# FPP_Connector.net
KiCad netlist of a schematic drawn in Altium Designer
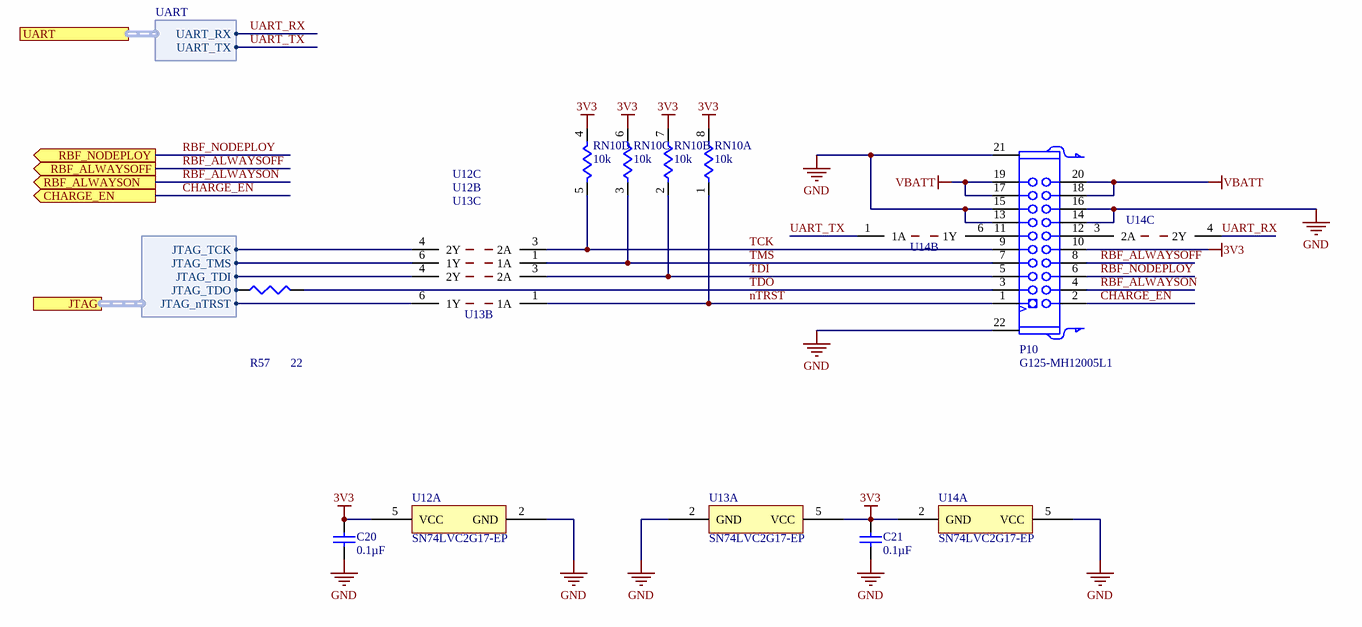
[diagram p0: FPP Connector.SchDoc]

(export (version "E")
  (design (tool "Eeschema 10.0.6"))
  (components
    (comp (ref "C20")
      (value "0.1µF")
      (footprint "TDK-CGA2B")
      (description "CAP CER 0.1UF 50V X7R 0402")
      (fields
        (field (name "PART NUMBER") "PC-TDK-02259")
        (field (name "MANUFACTURER PART NUMBER") "CGA2B3X7R1H104K050BB")
        (field (name "PUBLISHER") "AlbertaSat")
      )
      (libsource (lib "Database") (part "Cap"))
    )
    (comp (ref "C21")
      (value "0.1µF")
      (footprint "TDK-CGA2B")
      (description "CAP CER 0.1UF 50V X7R 0402")
      (fields
        (field (name "PART NUMBER") "PC-TDK-02259")
        (field (name "MANUFACTURER PART NUMBER") "CGA2B3X7R1H104K050BB")
        (field (name "PUBLISHER") "AlbertaSat")
      )
      (libsource (lib "Database") (part "Cap"))
    )
    (comp (ref "P10")
      (value "G125-MH12005L1")
      (footprint "HWN-G125-MH12005L1")
      (description "CONN HEADER R/A 20POS 1.25MM")
      (fields
        (field (name "PART NUMBER") "PP-HWN-00018")
        (field (name "MANUFACTURER PART NUMBER") "G125-MH12005L1P")
        (field (name "PUBLISHER") "AlbertaSat")
      )
      (libsource (lib "Database") (part "G125-MH12005L1P"))
    )
    (comp (ref "R57")
      (value "22")
      (footprint "PANA-ERJ2R")
      (description "RES SMD 22 OHM 1% 1/10W 0402")
      (fields
        (field (name "PART NUMBER") "13460")
        (field (name "MANUFACTURER PART NUMBER") "ERJ-2RKF22R0X")
        (field (name "PUBLISHER") "Altium Limited")
      )
      (libsource (lib "Database") (part "Res3"))
    )
    (comp (ref "RN10")
      (value "10k")
      (footprint "PANA-EXB28V")
      (description "RES ARRAY 4 RES 10K OHM 0804")
      (fields (field (name "PART NUMBER") "19968") (field (name "MANUFACTURER PART NUMBER") "EXB-28V103JX"))
      (libsource (lib "Database") (part "Res4 Pack1"))
    )
    (comp (ref "U12")
      (value "SN74LVC2G17-EP")
      (footprint "TI-R-PDSO-G6")
      (description "IC BUF NON-INVERT 5.5V SC70-6")
      (fields
        (field (name "PART NUMBER") "92")
        (field (name "MANUFACTURER PART NUMBER") "SN74LVC2G17MDCKREP")
      )
      (libsource (lib "Database") (part "SN74LVC2G17-EP"))
    )
    (comp (ref "U13")
      (value "SN74LVC2G17-EP")
      (footprint "TI-R-PDSO-G6")
      (description "IC BUF NON-INVERT 5.5V SC70-6")
      (fields
        (field (name "PART NUMBER") "92")
        (field (name "MANUFACTURER PART NUMBER") "SN74LVC2G17MDCKREP")
      )
      (libsource (lib "") (part "SN74LVC2G17-EP_2"))
    )
    (comp (ref "U14")
      (value "SN74LVC2G17-EP")
      (footprint "TI-R-PDSO-G6")
      (description "IC BUF NON-INVERT 5.5V SC70-6")
      (fields
        (field (name "PART NUMBER") "92")
        (field (name "MANUFACTURER PART NUMBER") "SN74LVC2G17MDCKREP")
      )
      (libsource (lib "Database") (part "SN74LVC2G17-EP"))
    )
  )
  (nets
    (net (code "3") (name "/CHARGE_EN") (class "Default")
      (node (ref "P10") (pin "2") (pinfunction "2_2") (pintype "passive"))
    )
    (net (code "4") (name "/JTAG_TCK") (class "Default")
      (node (ref "U12") (pin "4") (pinfunction "2Y_4") (pintype "passive"))
    )
    (net (code "5") (name "/JTAG_TDI") (class "Default")
      (node (ref "U13") (pin "4") (pinfunction "2Y_4") (pintype "passive"))
    )
    (net (code "6") (name "/JTAG_TDO") (class "Default")
      (node (ref "R57") (pin "1") (pinfunction "1_1") (pintype "passive"))
    )
    (net (code "7") (name "/JTAG_TMS") (class "Default")
      (node (ref "U12") (pin "6") (pinfunction "1Y_6") (pintype "passive"))
    )
    (net (code "8") (name "/JTAG_nTRST") (class "Default")
      (node (ref "U13") (pin "6") (pinfunction "1Y_6") (pintype "passive"))
    )
    (net (code "9") (name "/RBF_ALWAYSOFF") (class "Default")
      (node (ref "P10") (pin "8") (pinfunction "8_8") (pintype "passive"))
    )
    (net (code "10") (name "/RBF_ALWAYSON") (class "Default")
      (node (ref "P10") (pin "4") (pinfunction "4_4") (pintype "passive"))
    )
    (net (code "11") (name "/RBF_NODEPLOY") (class "Default")
      (node (ref "P10") (pin "6") (pinfunction "6_6") (pintype "passive"))
    )
    (net (code "12") (name "/TCK") (class "Default")
      (node (ref "P10") (pin "9") (pinfunction "9_9") (pintype "passive"))
      (node (ref "RN10") (pin "5") (pinfunction "5_5") (pintype "passive"))
      (node (ref "U12") (pin "3") (pinfunction "2A_3") (pintype "passive"))
    )
    (net (code "13") (name "/TDI") (class "Default")
      (node (ref "P10") (pin "5") (pinfunction "5_5") (pintype "passive"))
      (node (ref "RN10") (pin "2") (pinfunction "2_2") (pintype "passive"))
      (node (ref "U13") (pin "3") (pinfunction "2A_3") (pintype "passive"))
    )
    (net (code "14") (name "/TDO") (class "Default")
      (node (ref "P10") (pin "3") (pinfunction "3_3") (pintype "passive"))
      (node (ref "R57") (pin "2") (pinfunction "2_2") (pintype "passive"))
    )
    (net (code "15") (name "/TMS") (class "Default")
      (node (ref "P10") (pin "7") (pinfunction "7_7") (pintype "passive"))
      (node (ref "RN10") (pin "3") (pinfunction "3_3") (pintype "passive"))
      (node (ref "U12") (pin "1") (pinfunction "1A_1") (pintype "passive"))
    )
    (net (code "16") (name "/UART_RX") (class "Default")
      (node (ref "U14") (pin "4") (pinfunction "2Y_4") (pintype "passive"))
    )
    (net (code "17") (name "/UART_TX") (class "Default")
      (node (ref "U14") (pin "1") (pinfunction "1A_1") (pintype "passive"))
    )
    (net (code "18") (name "/nTRST") (class "Default")
      (node (ref "P10") (pin "1") (pinfunction "1_1") (pintype "passive"))
      (node (ref "RN10") (pin "1") (pinfunction "1_1") (pintype "passive"))
      (node (ref "U13") (pin "1") (pinfunction "1A_1") (pintype "passive"))
    )
    (net (code "21") (name "3V3") (class "Default")
      (node (ref "C20") (pin "1") (pinfunction "1_1") (pintype "passive"))
      (node (ref "C21") (pin "1") (pinfunction "1_1") (pintype "passive"))
      (node (ref "P10") (pin "10") (pinfunction "10_10") (pintype "passive"))
      (node (ref "RN10") (pin "4") (pinfunction "4_4") (pintype "passive"))
      (node (ref "RN10") (pin "6") (pinfunction "6_6") (pintype "passive"))
      (node (ref "RN10") (pin "7") (pinfunction "7_7") (pintype "passive"))
      (node (ref "RN10") (pin "8") (pinfunction "8_8") (pintype "passive"))
      (node (ref "U12") (pin "5") (pinfunction "VCC_5") (pintype "passive"))
      (node (ref "U13") (pin "5") (pinfunction "VCC_5") (pintype "passive"))
      (node (ref "U14") (pin "2") (pinfunction "GND_2") (pintype "passive"))
    )
    (net (code "22") (name "GND") (class "Default")
      (node (ref "C20") (pin "2") (pinfunction "2_2") (pintype "passive"))
      (node (ref "C21") (pin "2") (pinfunction "2_2") (pintype "passive"))
      (node (ref "P10") (pin "13") (pinfunction "13_13") (pintype "passive"))
      (node (ref "P10") (pin "14") (pinfunction "14_14") (pintype "passive"))
      (node (ref "P10") (pin "15") (pinfunction "15_15") (pintype "passive"))
      (node (ref "P10") (pin "16") (pinfunction "16_16") (pintype "passive"))
      (node (ref "P10") (pin "21") (pinfunction "21_21") (pintype "passive"))
      (node (ref "P10") (pin "22") (pinfunction "22_22") (pintype "passive"))
      (node (ref "U12") (pin "2") (pinfunction "GND_2") (pintype "passive"))
      (node (ref "U13") (pin "2") (pinfunction "GND_2") (pintype "passive"))
      (node (ref "U14") (pin "5") (pinfunction "VCC_5") (pintype "passive"))
    )
    (net (code "23") (name "Net-(U14B-1Y)") (class "Default")
      (node (ref "P10") (pin "11") (pinfunction "11_11") (pintype "passive"))
      (node (ref "U14") (pin "6") (pinfunction "1Y_6") (pintype "passive"))
    )
    (net (code "24") (name "Net-(U14C-2A)") (class "Default")
      (node (ref "P10") (pin "12") (pinfunction "12_12") (pintype "passive"))
      (node (ref "U14") (pin "3") (pinfunction "2A_3") (pintype "passive"))
    )
    (net (code "25") (name "VBATT") (class "Default")
      (node (ref "P10") (pin "17") (pinfunction "17_17") (pintype "passive"))
      (node (ref "P10") (pin "18") (pinfunction "18_18") (pintype "passive"))
      (node (ref "P10") (pin "19") (pinfunction "19_19") (pintype "passive"))
      (node (ref "P10") (pin "20") (pinfunction "20_20") (pintype "passive"))
    )
  )
)
